# DIGITAL_COUNTER.net
KiCad netlist of a schematic drawn in Altium Designer
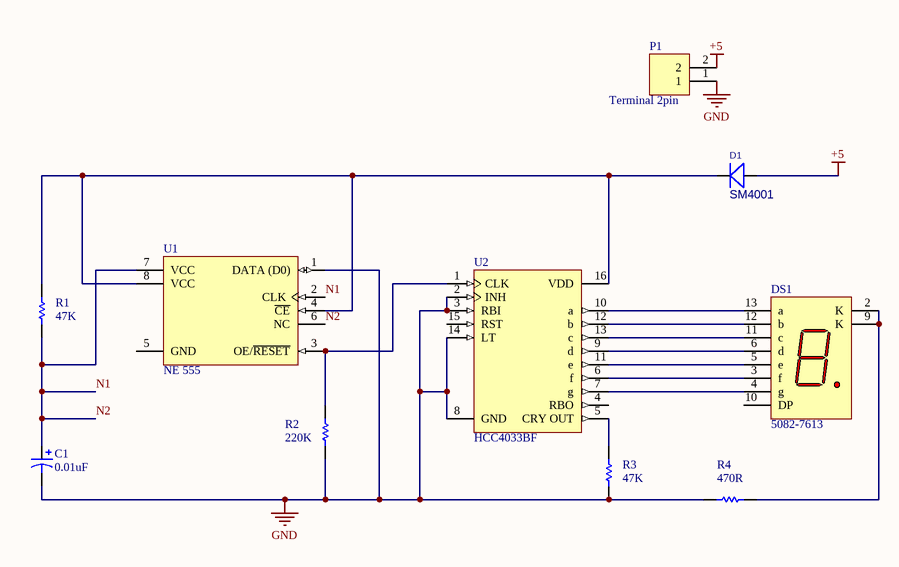
[diagram p0: DIGITAL COUNTER.SchDoc]

(export (version "E")
  (design (tool "Eeschema 10.0.6"))
  (components
    (comp (ref "C1") (value "0.01uF") (footprint "Cap 0810") (libsource (lib "My_LIB") (part "Cap 220uF")))
    (comp (ref "D1")
      (value "SM4001")
      (footprint "DIODE_DO-213AB")
      (description "Diode")
      (libsource (lib "My_LIB") (part "D_DO-213"))
    )
    (comp (ref "DS1")
      (value "5082-7613")
      (footprint "A-10(14)")
      (description "7.62 mm HER 7-Segment Display: CC, RH DP")
      (fields (field (name "PUBLISHER") "Altium Limited"))
      (libsource (lib "Agilent LED Display 7-Segment, 1-Digit") (part "5082-7613"))
    )
    (comp (ref "P1")
      (value "Terminal 2pin")
      (footprint "Terminal 2pin")
      (libsource (lib "My_LIB") (part "Terminal 2pin"))
    )
    (comp (ref "R1") (value "47K") (footprint "R_1206") (libsource (lib "My_LIB") (part "RES")))
    (comp (ref "R2") (value "220K") (footprint "R_1206") (libsource (lib "My_LIB") (part "RES")))
    (comp (ref "R3") (value "47K") (footprint "R_1206") (libsource (lib "My_LIB") (part "RES")))
    (comp (ref "R4") (value "470R") (footprint "R_1206") (libsource (lib "My_LIB") (part "RES")))
    (comp (ref "U1")
      (value "NE 555")
      (footprint "SO-8")
      (fields (field (name "PUBLISHER") "Altium Limited"))
      (libsource (lib "Xilinx XC17S00") (part "XC17S05VO8C"))
    )
    (comp (ref "U2")
      (value "HCC4033BF")
      (footprint "SOIC16_M")
      (description "Decade Counter / Divider with Decoded 7-Segment Display Output")
      (fields (field (name "PUBLISHER") "Altium Limited"))
      (libsource (lib "ST Interface Display Driver") (part "HCC4033BF"))
    )
  )
  (nets
    (net (code "1") (name "+5") (class "Default")
      (node (ref "D1") (pin "1") (pinfunction "A_1") (pintype "passive"))
      (node (ref "P1") (pin "2") (pinfunction "2_2") (pintype "passive"))
    )
    (net (code "2") (name "/N1") (class "Default")
      (node (ref "C1") (pin "1") (pinfunction "1_1") (pintype "passive"))
      (node (ref "R1") (pin "1") (pinfunction "1_1") (pintype "passive"))
      (node (ref "U1") (pin "2") (pinfunction "CLK_2") (pintype "input"))
      (node (ref "U1") (pin "6") (pinfunction "NC_6") (pintype "passive"))
      (node (ref "U1") (pin "7") (pinfunction "VCC_7") (pintype "power_in"))
    )
    (net (code "3") (name "GND") (class "Default")
      (node (ref "C1") (pin "2") (pinfunction "2_2") (pintype "passive"))
      (node (ref "P1") (pin "1") (pinfunction "1_1") (pintype "passive"))
      (node (ref "R2") (pin "2") (pinfunction "2_2") (pintype "passive"))
      (node (ref "R3") (pin "2") (pinfunction "2_2") (pintype "passive"))
      (node (ref "R4") (pin "2") (pinfunction "2_2") (pintype "passive"))
      (node (ref "U1") (pin "1") (pinfunction "DATA_(D0)_1") (pintype "bidirectional"))
      (node (ref "U2") (pin "14") (pinfunction "LT_14") (pintype "input"))
      (node (ref "U2") (pin "2") (pinfunction "INH_2") (pintype "input"))
      (node (ref "U2") (pin "3") (pinfunction "RBI_3") (pintype "input"))
      (node (ref "U2") (pin "8") (pinfunction "GND_8") (pintype "power_in"))
    )
    (net (code "4") (name "Net-(D1-K)") (class "Default")
      (node (ref "D1") (pin "2") (pinfunction "K_2") (pintype "passive"))
      (node (ref "R1") (pin "2") (pinfunction "2_2") (pintype "passive"))
      (node (ref "U1") (pin "4") (pinfunction "~{CE}_4") (pintype "input"))
      (node (ref "U1") (pin "8") (pinfunction "VCC_8") (pintype "power_in"))
      (node (ref "U2") (pin "16") (pinfunction "VDD_16") (pintype "power_in"))
    )
    (net (code "5") (name "Net-(DS1-K-Pad2)") (class "Default")
      (node (ref "DS1") (pin "2") (pinfunction "K_2") (pintype "passive"))
      (node (ref "DS1") (pin "9") (pinfunction "K_9") (pintype "passive"))
      (node (ref "R4") (pin "1") (pinfunction "1_1") (pintype "passive"))
    )
    (net (code "6") (name "Net-(DS1-a)") (class "Default")
      (node (ref "DS1") (pin "13") (pinfunction "a_13") (pintype "passive"))
      (node (ref "U2") (pin "10") (pinfunction "a_10") (pintype "output"))
    )
    (net (code "7") (name "Net-(DS1-b)") (class "Default")
      (node (ref "DS1") (pin "12") (pinfunction "b_12") (pintype "passive"))
      (node (ref "U2") (pin "12") (pinfunction "b_12") (pintype "output"))
    )
    (net (code "8") (name "Net-(DS1-c)") (class "Default")
      (node (ref "DS1") (pin "11") (pinfunction "c_11") (pintype "passive"))
      (node (ref "U2") (pin "13") (pinfunction "c_13") (pintype "output"))
    )
    (net (code "9") (name "Net-(DS1-d)") (class "Default")
      (node (ref "DS1") (pin "6") (pinfunction "d_6") (pintype "passive"))
      (node (ref "U2") (pin "9") (pinfunction "d_9") (pintype "output"))
    )
    (net (code "10") (name "Net-(DS1-e)") (class "Default")
      (node (ref "DS1") (pin "5") (pinfunction "e_5") (pintype "passive"))
      (node (ref "U2") (pin "11") (pinfunction "e_11") (pintype "output"))
    )
    (net (code "11") (name "Net-(DS1-f)") (class "Default")
      (node (ref "DS1") (pin "3") (pinfunction "f_3") (pintype "passive"))
      (node (ref "U2") (pin "6") (pinfunction "f_6") (pintype "output"))
    )
    (net (code "12") (name "Net-(DS1-g)") (class "Default")
      (node (ref "DS1") (pin "4") (pinfunction "g_4") (pintype "passive"))
      (node (ref "U2") (pin "7") (pinfunction "g_7") (pintype "output"))
    )
    (net (code "13") (name "Net-(U1-OE{slash}~{RESET})") (class "Default")
      (node (ref "R2") (pin "1") (pinfunction "1_1") (pintype "passive"))
      (node (ref "U1") (pin "3") (pinfunction "OE/~{RESET}_3") (pintype "input"))
      (node (ref "U2") (pin "1") (pinfunction "CLK_1") (pintype "input"))
    )
    (net (code "14") (name "Net-(U2-CRY_OUT)") (class "Default")
      (node (ref "R3") (pin "1") (pinfunction "1_1") (pintype "passive"))
      (node (ref "U2") (pin "5") (pinfunction "CRY_OUT_5") (pintype "output"))
    )
    (net (code "15") (name "unconnected-(DS1-DP-Pad10)") (class "Default")
      (node (ref "DS1") (pin "10") (pinfunction "DP_10") (pintype "passive"))
    )
    (net (code "16") (name "unconnected-(U1-GND-Pad5)") (class "Default")
      (node (ref "U1") (pin "5") (pinfunction "GND_5") (pintype "power_in"))
    )
    (net (code "17") (name "unconnected-(U2-RBO-Pad4)") (class "Default")
      (node (ref "U2") (pin "4") (pinfunction "RBO_4") (pintype "output"))
    )
    (net (code "18") (name "unconnected-(U2-RST-Pad15)") (class "Default")
      (node (ref "U2") (pin "15") (pinfunction "RST_15") (pintype "input"))
    )
  )
)
